# uPre_V2.net
KiCad netlist of a schematic drawn in Altium Designer
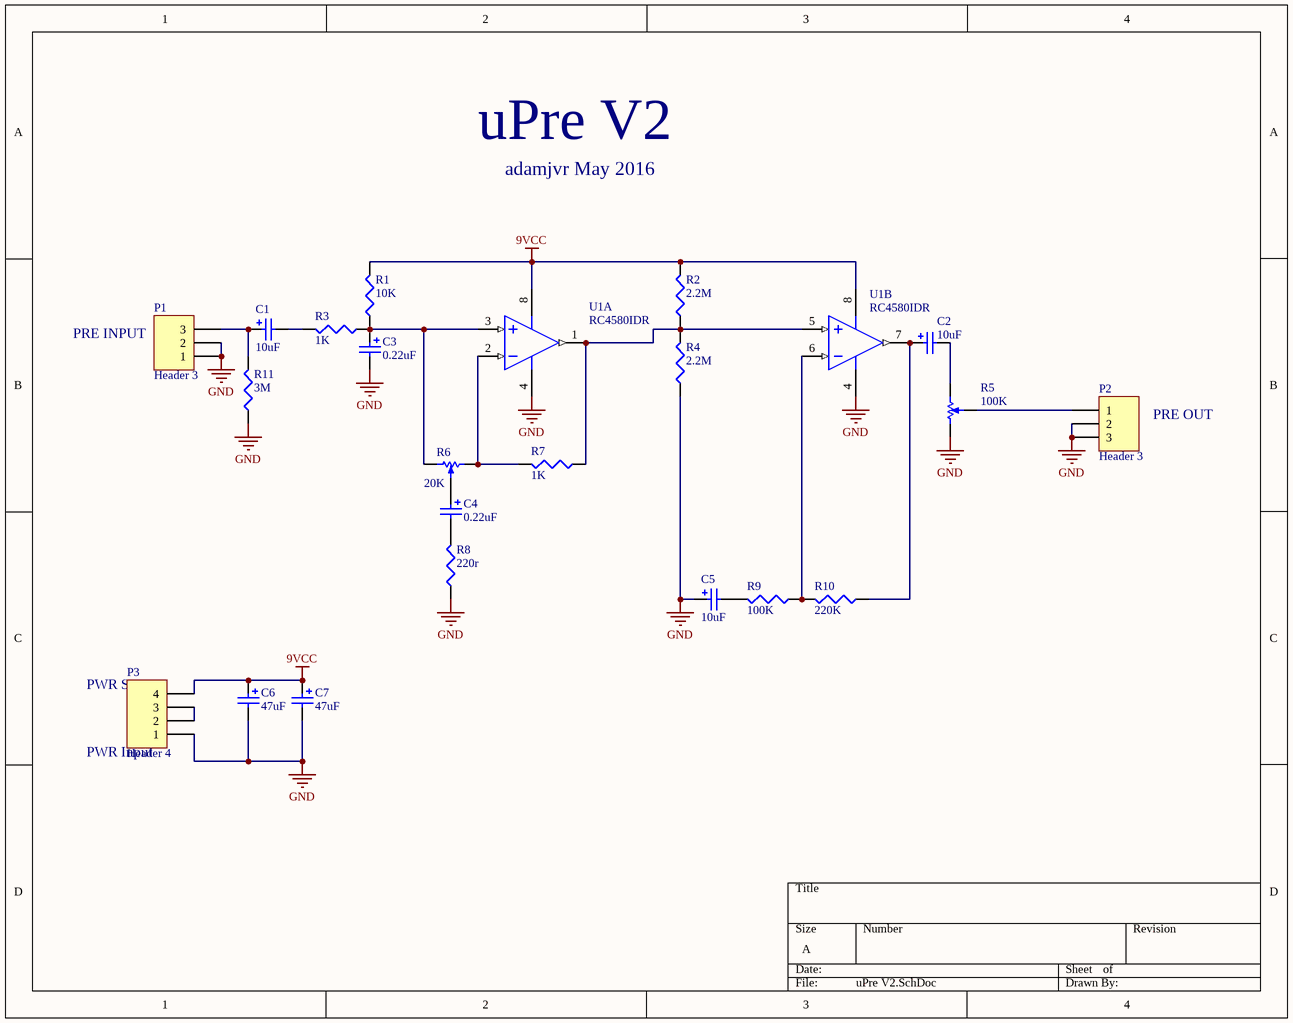
[diagram p0: uPre V2.SchDoc]

(export (version "E")
  (design (tool "Eeschema 10.0.6"))
  (components
    (comp (ref "C1")
      (value "10uF")
      (footprint "4X6mmCAP")
      (description "CAP ALUM 10UF 20% 16V RADIAL")
      (fields
        (field (name "MFR") "Nichicon")
        (field (name "TOLERANCE") "20%")
        (field (name "DESIGNER") "Adam Vadala-Roth")
      )
      (libsource (lib "AudioPartLib") (part "UMW1C100MDD1TP"))
    )
    (comp (ref "C2")
      (value "10uF")
      (footprint "4X6mmCAP")
      (description "CAP ALUM 10UF 20% 16V RADIAL")
      (fields
        (field (name "MFR") "Nichicon")
        (field (name "TOLERANCE") "20%")
        (field (name "DESIGNER") "Adam Vadala-Roth")
      )
      (libsource (lib "AudioPartLib") (part "UMW1C100MDD1TP"))
    )
    (comp (ref "C3")
      (value "0.22uF")
      (footprint "4X6mmCAP")
      (description "CAP ALUM 0.22UF 20% 50V RADIAL")
      (fields
        (field (name "MFR") "Nichicon")
        (field (name "TOLERANCE") "20%")
        (field (name "DESIGNER") "Adam Vadala-Roth")
      )
      (libsource (lib "AudioPartLib") (part "UMW1HR22MDD1TP"))
    )
    (comp (ref "C4")
      (value "0.22uF")
      (footprint "4X6mmCAP")
      (description "CAP ALUM 0.22UF 20% 50V RADIAL")
      (fields
        (field (name "MFR") "Nichicon")
        (field (name "TOLERANCE") "20%")
        (field (name "DESIGNER") "Adam Vadala-Roth")
      )
      (libsource (lib "AudioPartLib") (part "UMW1HR22MDD1TP"))
    )
    (comp (ref "C5")
      (value "10uF")
      (footprint "4X6mmCAP")
      (description "CAP ALUM 10UF 20% 16V RADIAL")
      (fields
        (field (name "MFR") "Nichicon")
        (field (name "TOLERANCE") "20%")
        (field (name "DESIGNER") "Adam Vadala-Roth")
      )
      (libsource (lib "AudioPartLib") (part "UMW1C100MDD1TP"))
    )
    (comp (ref "C6")
      (value "47uF")
      (footprint "5X12.5mmCAP - BLUE")
      (description "CAP ALUM 47UF 20% 25V RADIAL")
      (fields
        (field (name "MFR") "Nichicon")
        (field (name "TOLERANCE") "20%")
        (field (name "DESIGNER") "Adam Vadala-Roth")
      )
      (libsource (lib "AudioPartLib") (part "UKA1E470MDD1TD"))
    )
    (comp (ref "C7")
      (value "47uF")
      (footprint "5X12.5mmCAP - BLUE")
      (description "CAP ALUM 47UF 20% 25V RADIAL")
      (fields
        (field (name "MFR") "Nichicon")
        (field (name "TOLERANCE") "20%")
        (field (name "DESIGNER") "Adam Vadala-Roth")
      )
      (libsource (lib "AudioPartLib") (part "UKA1E470MDD1TD"))
    )
    (comp (ref "P1")
      (value "Header 3")
      (footprint "HDR1X3")
      (description "Header, 3-Pin")
      (fields (field (name "PUBLISHER") "Altium Limited"))
      (libsource (lib "") (part "Header 3_1"))
    )
    (comp (ref "P2")
      (value "Header 3")
      (footprint "HDR1X3")
      (description "Header, 3-Pin")
      (fields (field (name "PUBLISHER") "Altium Limited"))
      (libsource (lib "Miscellaneous Connectors") (part "Header 3"))
    )
    (comp (ref "P3")
      (value "Header 4")
      (footprint "HDR1X4")
      (description "Header, 4-Pin")
      (fields (field (name "PUBLISHER") "Altium Limited"))
      (libsource (lib "Miscellaneous Connectors") (part "Header 4"))
    )
    (comp (ref "R1")
      (value "10K")
      (footprint "R0805")
      (description "RES SMD 10K OHM 1% 1/8W 0805")
      (fields
        (field (name "MFR") "Panasonic-Electronic-Components")
        (field (name "TOLERANCE") "1%")
        (field (name "DESIGNER") "Adam Vadala-Roth")
      )
      (libsource (lib "AudioPartLib") (part "ERJ-6ENF1002V"))
    )
    (comp (ref "R2")
      (value "2.2M")
      (footprint "R0805")
      (description "RES SMD 2.2M OHM 1% 1/8W 0805")
      (fields
        (field (name "MFR") "Samsung-Electro-Mechanics-America,-Inc.")
        (field (name "TOLERANCE") "1%")
        (field (name "DESIGNER") "Adam Vadala-Roth")
      )
      (libsource (lib "AudioPartLib") (part "RC2012F225CS"))
    )
    (comp (ref "R3")
      (value "1K")
      (footprint "R0805")
      (description "RES SMD 1K OHM 1% 1/8W 0805")
      (fields
        (field (name "MFR") "Samsung-Electro-Mechanics-America,-Inc.")
        (field (name "TOLERANCE") "1%")
        (field (name "DESIGNER") "Adam Vadala-Roth")
      )
      (libsource (lib "AudioPartLib") (part "RC2012F102CS"))
    )
    (comp (ref "R4")
      (value "2.2M")
      (footprint "R0805")
      (description "RES SMD 2.2M OHM 1% 1/8W 0805")
      (fields
        (field (name "MFR") "Samsung-Electro-Mechanics-America,-Inc.")
        (field (name "TOLERANCE") "1%")
        (field (name "DESIGNER") "Adam Vadala-Roth")
      )
      (libsource (lib "AudioPartLib") (part "RC2012F225CS"))
    )
    (comp (ref "R5")
      (value "100K")
      (footprint "BOURNS_PTD90SERIES_POT")
      (description "POT 100K OHM 1/20W CARBON LINEAR")
      (fields
        (field (name "MFR") "Bourns Inc.")
        (field (name "TOLERANCE") "20%")
        (field (name "DESIGNER") "Adam Vadala-Roth")
      )
      (libsource (lib "AudioPartLib") (part "PTD901-2015K-B104"))
    )
    (comp (ref "R6")
      (value "20K")
      (footprint "BOURNS_PTD90SERIES_POT")
      (description "POT 20K OHM 1/20W CARBON LINEAR")
      (fields
        (field (name "MFR") "Bourns Inc.")
        (field (name "TOLERANCE") "20%")
        (field (name "DESIGNER") "Adam Vadala-Roth")
      )
      (libsource (lib "AudioPartLib") (part "PTD901-2015K-B203"))
    )
    (comp (ref "R7")
      (value "1K")
      (footprint "R0805")
      (description "RES SMD 1K OHM 1% 1/8W 0805")
      (fields
        (field (name "MFR") "Samsung-Electro-Mechanics-America,-Inc.")
        (field (name "TOLERANCE") "1%")
        (field (name "DESIGNER") "Adam Vadala-Roth")
      )
      (libsource (lib "AudioPartLib") (part "RC2012F102CS"))
    )
    (comp (ref "R8")
      (value "220r")
      (footprint "R0805")
      (description "RES SMD 220 OHM 1% 1/8W 0805")
      (fields
        (field (name "MFR") "Samsung-Electro-Mechanics-America,-Inc.")
        (field (name "TOLERANCE") "5%")
        (field (name "DESIGNER") "Adam Vadala-Roth")
      )
      (libsource (lib "AudioPartLib") (part "RC2012F221CS"))
    )
    (comp (ref "R9")
      (value "100K")
      (footprint "R0805")
      (description "RES SMD 100K OHM 1% 1/8W 0805")
      (fields
        (field (name "MFR") "Panasonic-Electronic-Components")
        (field (name "TOLERANCE") "1%")
        (field (name "DESIGNER") "Adam Vadala-Roth")
      )
      (libsource (lib "AudioPartLib") (part "ERJ-6ENF1003V"))
    )
    (comp (ref "R10")
      (value "220K")
      (footprint "R0805")
      (description "RES SMD 220K OHM 1% 1/8W 0805")
      (fields
        (field (name "MFR") "Samsung-Electro-Mechanics-America,-Inc.")
        (field (name "TOLERANCE") "1%")
        (field (name "DESIGNER") "Adam Vadala-Roth")
      )
      (libsource (lib "AudioPartLib") (part "RC2012F224CS"))
    )
    (comp (ref "R11")
      (value "3M")
      (footprint "R0805")
      (description "RES SMD 3M OHM 1% 1/8W 0805")
      (fields
        (field (name "MFR") "Samsung-Electro-Mechanics-America,-Inc.")
        (field (name "TOLERANCE") "1%")
        (field (name "DESIGNER") "Adam Vadala-Roth")
      )
      (libsource (lib "AudioPartLib") (part "RC2012F305CS"))
    )
    (comp (ref "U1")
      (value "RC4580IDR")
      (footprint "SOIC127P600X175-8N")
      (fields
        (field (name "MFR") "Texas Instruments")
        (field (name "VOLTAGE") "16V Max")
        (field (name "DESIGNER") "Adam Vadala-Roth")
      )
      (libsource (lib "AudioPartLib") (part "RC4580IDR"))
    )
  )
  (nets
    (net (code "1") (name "9VCC") (class "Default")
      (node (ref "C6") (pin "1") (pinfunction "1_1") (pintype "passive"))
      (node (ref "C7") (pin "1") (pinfunction "1_1") (pintype "passive"))
      (node (ref "P3") (pin "4") (pinfunction "4_4") (pintype "passive"))
      (node (ref "R1") (pin "2") (pinfunction "2_2") (pintype "passive"))
      (node (ref "R2") (pin "2") (pinfunction "2_2") (pintype "passive"))
      (node (ref "U1") (pin "8") (pinfunction "V+_8") (pintype "power_in"))
    )
    (net (code "2") (name "GND") (class "Default")
      (node (ref "C3") (pin "2") (pinfunction "2_2") (pintype "passive"))
      (node (ref "C5") (pin "1") (pinfunction "1_1") (pintype "passive"))
      (node (ref "C6") (pin "2") (pinfunction "2_2") (pintype "passive"))
      (node (ref "C7") (pin "2") (pinfunction "2_2") (pintype "passive"))
      (node (ref "P1") (pin "1") (pinfunction "1_1") (pintype "passive"))
      (node (ref "P1") (pin "2") (pinfunction "2_2") (pintype "passive"))
      (node (ref "P2") (pin "2") (pinfunction "2_2") (pintype "passive"))
      (node (ref "P2") (pin "3") (pinfunction "3_3") (pintype "passive"))
      (node (ref "P3") (pin "1") (pinfunction "1_1") (pintype "passive"))
      (node (ref "R11") (pin "1") (pinfunction "1_1") (pintype "passive"))
      (node (ref "R4") (pin "1") (pinfunction "1_1") (pintype "passive"))
      (node (ref "R5") (pin "3") (pinfunction "3_3") (pintype "passive"))
      (node (ref "R8") (pin "1") (pinfunction "1_1") (pintype "passive"))
      (node (ref "U1") (pin "4") (pinfunction "V-_4") (pintype "power_in"))
    )
    (net (code "3") (name "Net-(C1-Pad1)") (class "Default")
      (node (ref "C1") (pin "1") (pinfunction "1_1") (pintype "passive"))
      (node (ref "P1") (pin "3") (pinfunction "3_3") (pintype "passive"))
      (node (ref "R11") (pin "2") (pinfunction "2_2") (pintype "passive"))
    )
    (net (code "4") (name "Net-(C1-Pad2)") (class "Default")
      (node (ref "C1") (pin "2") (pinfunction "2_2") (pintype "passive"))
      (node (ref "R3") (pin "2") (pinfunction "2_2") (pintype "passive"))
    )
    (net (code "5") (name "Net-(C2-Pad2)") (class "Default")
      (node (ref "C2") (pin "2") (pinfunction "2_2") (pintype "passive"))
      (node (ref "R5") (pin "1") (pinfunction "1_1") (pintype "passive"))
    )
    (net (code "6") (name "Net-(C3-Pad1)") (class "Default")
      (node (ref "C3") (pin "1") (pinfunction "1_1") (pintype "passive"))
      (node (ref "R1") (pin "1") (pinfunction "1_1") (pintype "passive"))
      (node (ref "R3") (pin "1") (pinfunction "1_1") (pintype "passive"))
      (node (ref "R6") (pin "3") (pinfunction "3_3") (pintype "passive"))
      (node (ref "U1") (pin "3") (pinfunction "IN_A_3") (pintype "input"))
    )
    (net (code "7") (name "Net-(C4-Pad1)") (class "Default")
      (node (ref "C4") (pin "1") (pinfunction "1_1") (pintype "passive"))
      (node (ref "R6") (pin "2") (pinfunction "2_2") (pintype "passive"))
    )
    (net (code "8") (name "Net-(C4-Pad2)") (class "Default")
      (node (ref "C4") (pin "2") (pinfunction "2_2") (pintype "passive"))
      (node (ref "R8") (pin "2") (pinfunction "2_2") (pintype "passive"))
    )
    (net (code "9") (name "Net-(C5-Pad2)") (class "Default")
      (node (ref "C5") (pin "2") (pinfunction "2_2") (pintype "passive"))
      (node (ref "R9") (pin "2") (pinfunction "2_2") (pintype "passive"))
    )
    (net (code "10") (name "Net-(P2-Pad1)") (class "Default")
      (node (ref "P2") (pin "1") (pinfunction "1_1") (pintype "passive"))
      (node (ref "R5") (pin "2") (pinfunction "2_2") (pintype "passive"))
    )
    (net (code "11") (name "Net-(P3-Pad2)") (class "Default")
      (node (ref "P3") (pin "2") (pinfunction "2_2") (pintype "passive"))
      (node (ref "P3") (pin "3") (pinfunction "3_3") (pintype "passive"))
    )
    (net (code "12") (name "Net-(R6-Pad1)") (class "Default")
      (node (ref "R6") (pin "1") (pinfunction "1_1") (pintype "passive"))
      (node (ref "R7") (pin "2") (pinfunction "2_2") (pintype "passive"))
      (node (ref "U1") (pin "2") (pinfunction "IN_A_2") (pintype "input"))
    )
    (net (code "13") (name "Net-(R10-Pad2)") (class "Default")
      (node (ref "R10") (pin "2") (pinfunction "2_2") (pintype "passive"))
      (node (ref "R9") (pin "1") (pinfunction "1_1") (pintype "passive"))
      (node (ref "U1") (pin "6") (pinfunction "IN_B_6") (pintype "input"))
    )
    (net (code "14") (name "Net-(U1A-OUT_A)") (class "Default")
      (node (ref "R2") (pin "1") (pinfunction "1_1") (pintype "passive"))
      (node (ref "R4") (pin "2") (pinfunction "2_2") (pintype "passive"))
      (node (ref "R7") (pin "1") (pinfunction "1_1") (pintype "passive"))
      (node (ref "U1") (pin "1") (pinfunction "OUT_A_1") (pintype "output"))
      (node (ref "U1") (pin "5") (pinfunction "IN_B_5") (pintype "input"))
    )
    (net (code "15") (name "Net-(U1B-OUT_B)") (class "Default")
      (node (ref "C2") (pin "1") (pinfunction "1_1") (pintype "passive"))
      (node (ref "R10") (pin "1") (pinfunction "1_1") (pintype "passive"))
      (node (ref "U1") (pin "7") (pinfunction "OUT_B_7") (pintype "output"))
    )
  )
)
